# ProProject_FPC_SHT4x_LPS22_2024-05-12.net
KiCad netlist of a schematic drawn in EasyEDA Pro
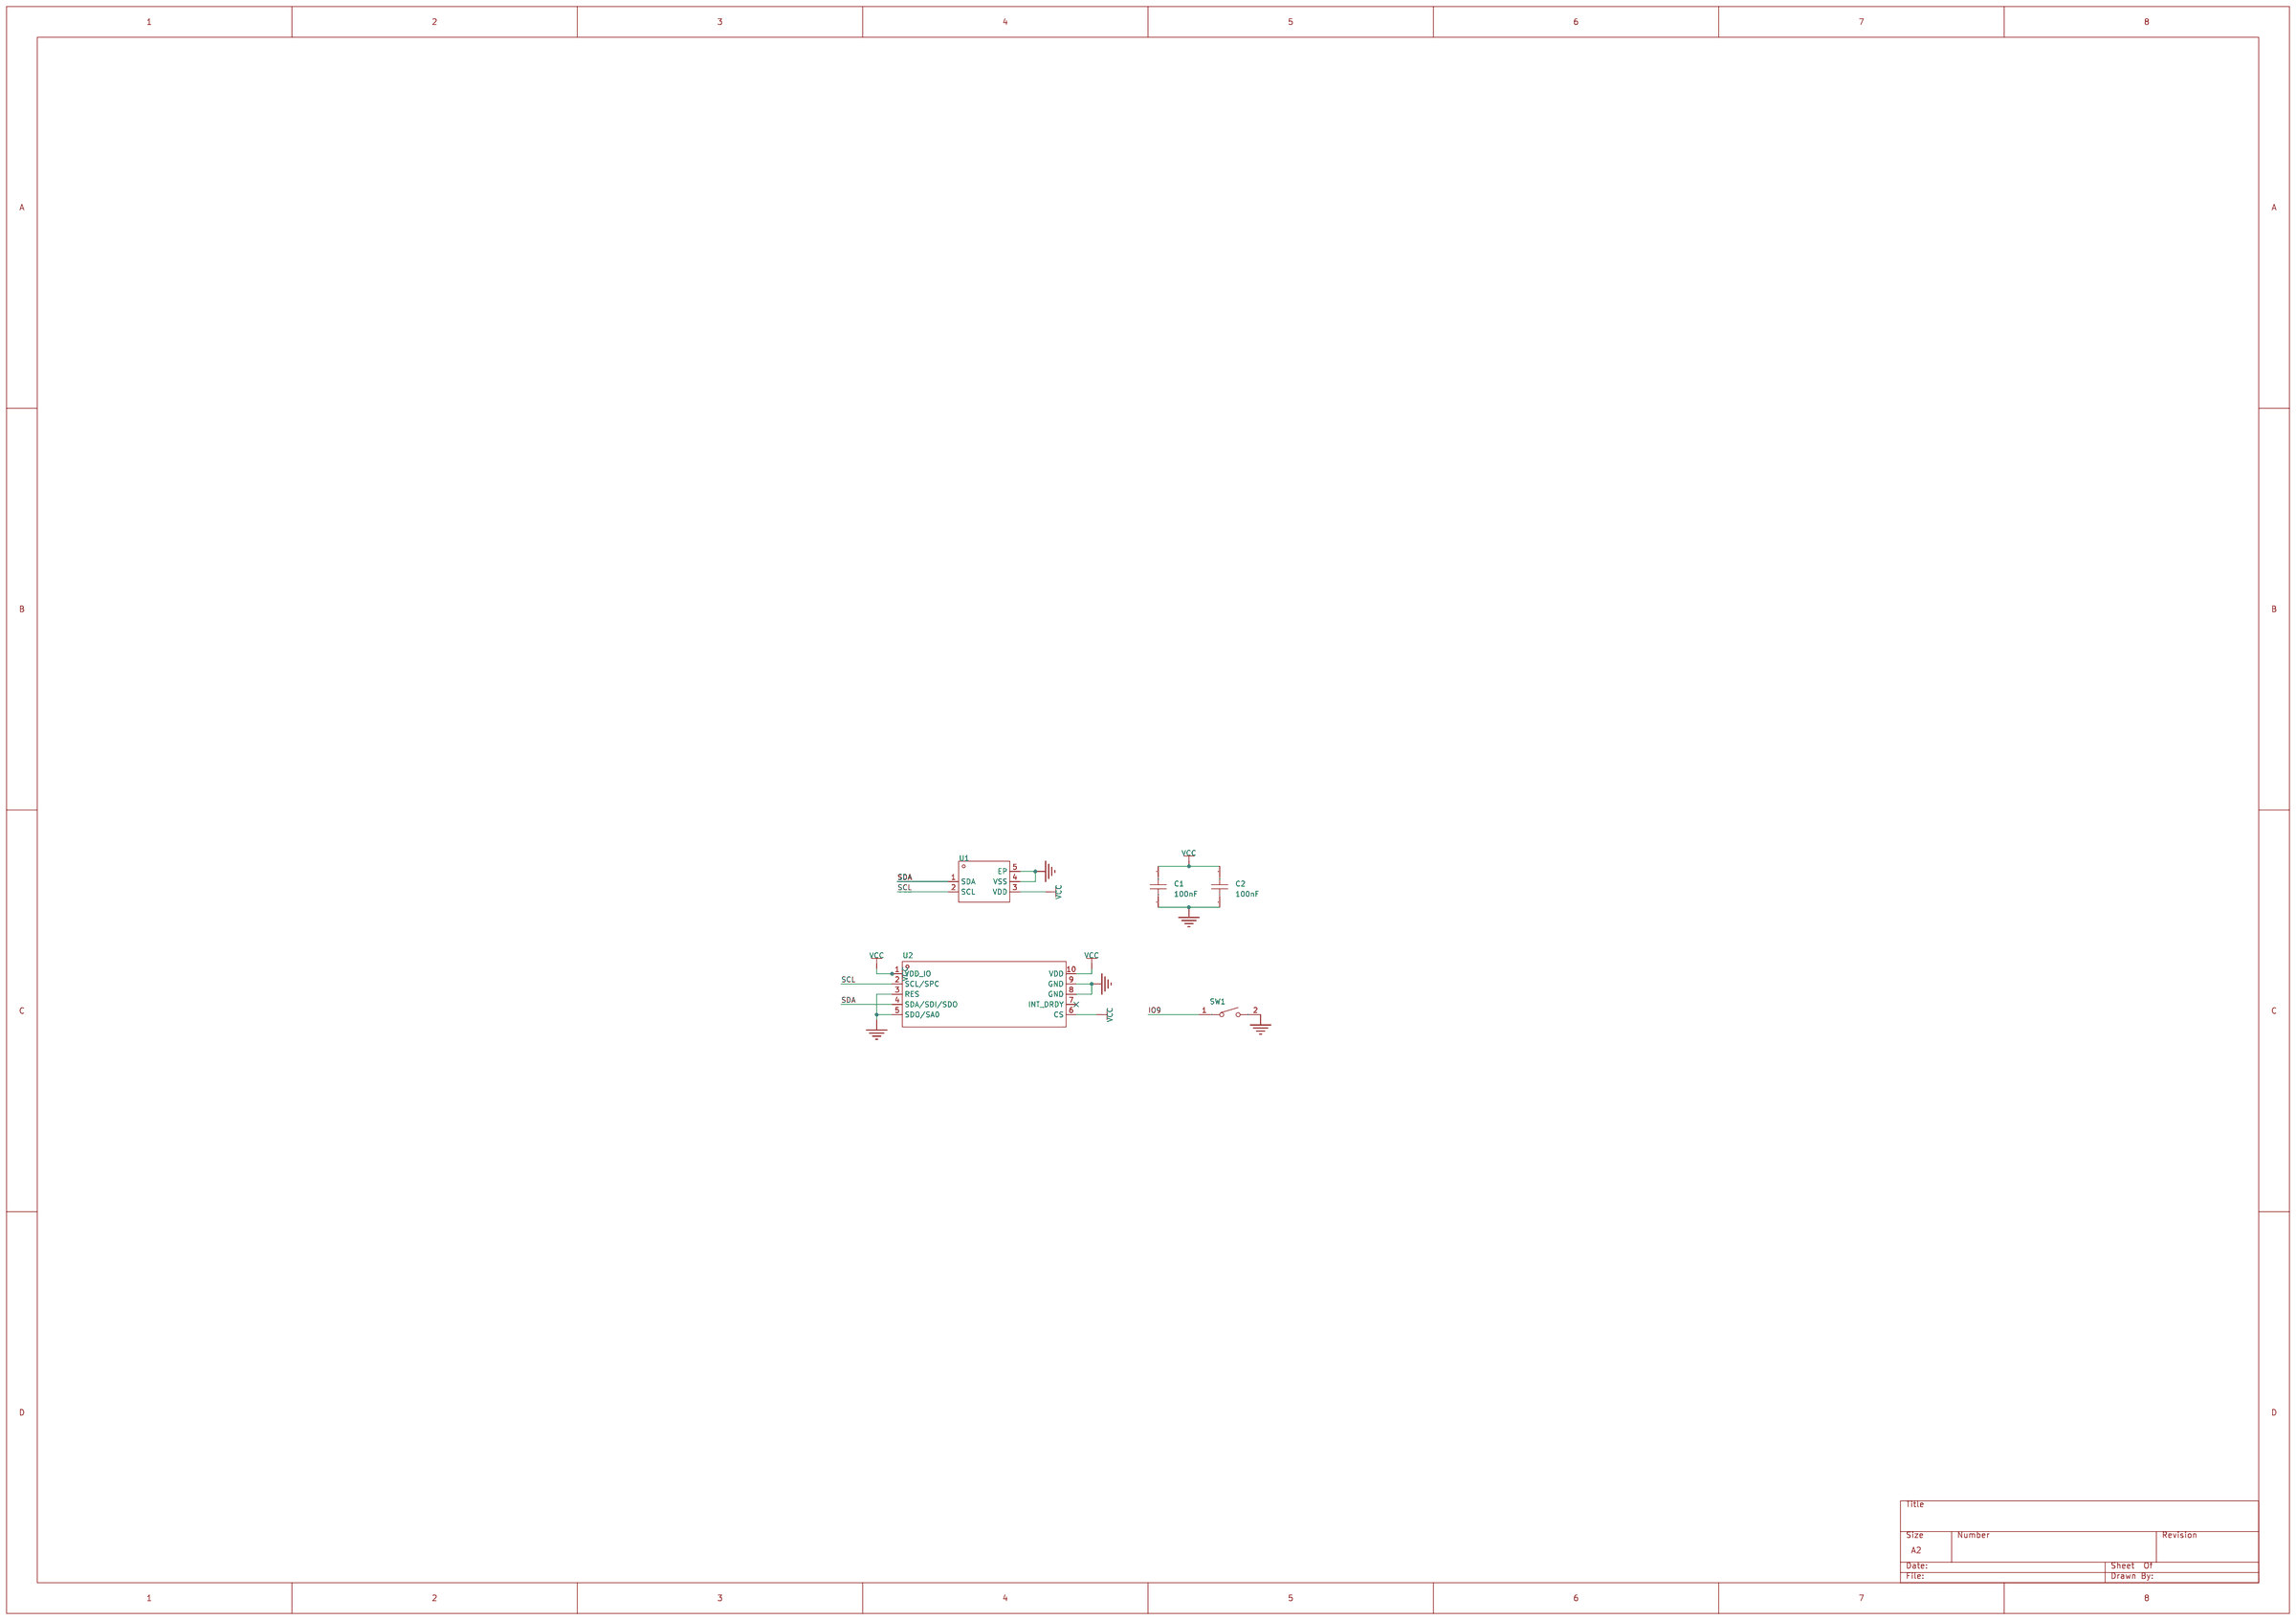
[diagram p0: schematic sheet]

(export (version "E")
  (design (tool "Eeschema 10.0.6"))
  (components
    (comp (ref "C1")
      (value "100nF")
      (footprint "easyedapro:C0402")
      (libsource (lib "easyedapro") (part "CapAcitance"))
    )
    (comp (ref "C2")
      (value "100nF")
      (footprint "easyedapro:C0402")
      (libsource (lib "easyedapro") (part "CapAcitance"))
    )
    (comp (ref "SW1")
      (value "TS-1088-AR02016")
      (footprint "easyedapro:SW-SMD_L3.9-W3.0-P4.45")
      (fields (field (name "Manufacturer") "XUNPU(讯普)"))
      (libsource (lib "easyedapro") (part "TS-1088-AR02016"))
    )
    (comp (ref "U1")
      (value "SHT40-AD1B-R2")
      (footprint "easyedapro:DFN-4_L1.5-W1.5-P0.8-TL-EP")
      (description "±1.8% / max. ±3.5% RH 数字温湿度传感器")
      (fields (field (name "Manufacturer") "Sensirion(瑞士盛思锐)"))
      (libsource (lib "easyedapro") (part "SHT40-AD1B-R2"))
    )
    (comp (ref "U2")
      (value "LPS22HBTR")
      (footprint "easyedapro:HLGA-10L_LPS22HBTR")
      (description "压力范围:26Kpa~126Kpa;")
      (fields (field (name "Manufacturer") "ST(意法半导体)"))
      (libsource (lib "easyedapro") (part "LPS22HBTR"))
    )
  )
  (nets
    (net (code "1") (name "/IO9") (class "Default")
      (node (ref "SW1") (pin "1") (pinfunction "1_1") (pintype "unspecified"))
    )
    (net (code "2") (name "/SCL") (class "Default")
      (node (ref "U1") (pin "2") (pinfunction "SCL_2") (pintype "unspecified"))
      (node (ref "U2") (pin "2") (pinfunction "SCL/SPC_2") (pintype "unspecified"))
    )
    (net (code "3") (name "/SDA") (class "Default")
      (node (ref "U1") (pin "1") (pinfunction "SDA_1") (pintype "unspecified"))
      (node (ref "U2") (pin "4") (pinfunction "SDA/SDI/SDO_4") (pintype "unspecified"))
    )
    (net (code "4") (name "GND") (class "Default")
      (node (ref "C1") (pin "1") (pinfunction "1_1") (pintype "input"))
      (node (ref "C2") (pin "1") (pinfunction "1_1") (pintype "input"))
      (node (ref "SW1") (pin "2") (pinfunction "2_2") (pintype "unspecified"))
      (node (ref "U1") (pin "4") (pinfunction "VSS_4") (pintype "unspecified"))
      (node (ref "U1") (pin "5") (pinfunction "EP_5") (pintype "unspecified"))
      (node (ref "U2") (pin "3") (pinfunction "RES_3") (pintype "unspecified"))
      (node (ref "U2") (pin "5") (pinfunction "SDO/SA0_5") (pintype "unspecified"))
      (node (ref "U2") (pin "8") (pinfunction "GND_8") (pintype "unspecified"))
      (node (ref "U2") (pin "9") (pinfunction "GND_9") (pintype "unspecified"))
    )
    (net (code "5") (name "VCC") (class "Default")
      (node (ref "C1") (pin "2") (pinfunction "2_2") (pintype "input"))
      (node (ref "C2") (pin "2") (pinfunction "2_2") (pintype "input"))
      (node (ref "U1") (pin "3") (pinfunction "VDD_3") (pintype "unspecified"))
      (node (ref "U2") (pin "1") (pinfunction "VDD_IO_1") (pintype "unspecified"))
      (node (ref "U2") (pin "10") (pinfunction "VDD_10") (pintype "unspecified"))
      (node (ref "U2") (pin "6") (pinfunction "CS_6") (pintype "unspecified"))
    )
    (net (code "6") (name "unconnected-(U2-INT_DRDY-Pad7)") (class "Default")
      (node (ref "U2") (pin "7") (pinfunction "INT_DRDY_7") (pintype "unspecified+no_connect"))
    )
  )
)
